# schematic.net
KiCad netlist of a schematic drawn in Altium Designer
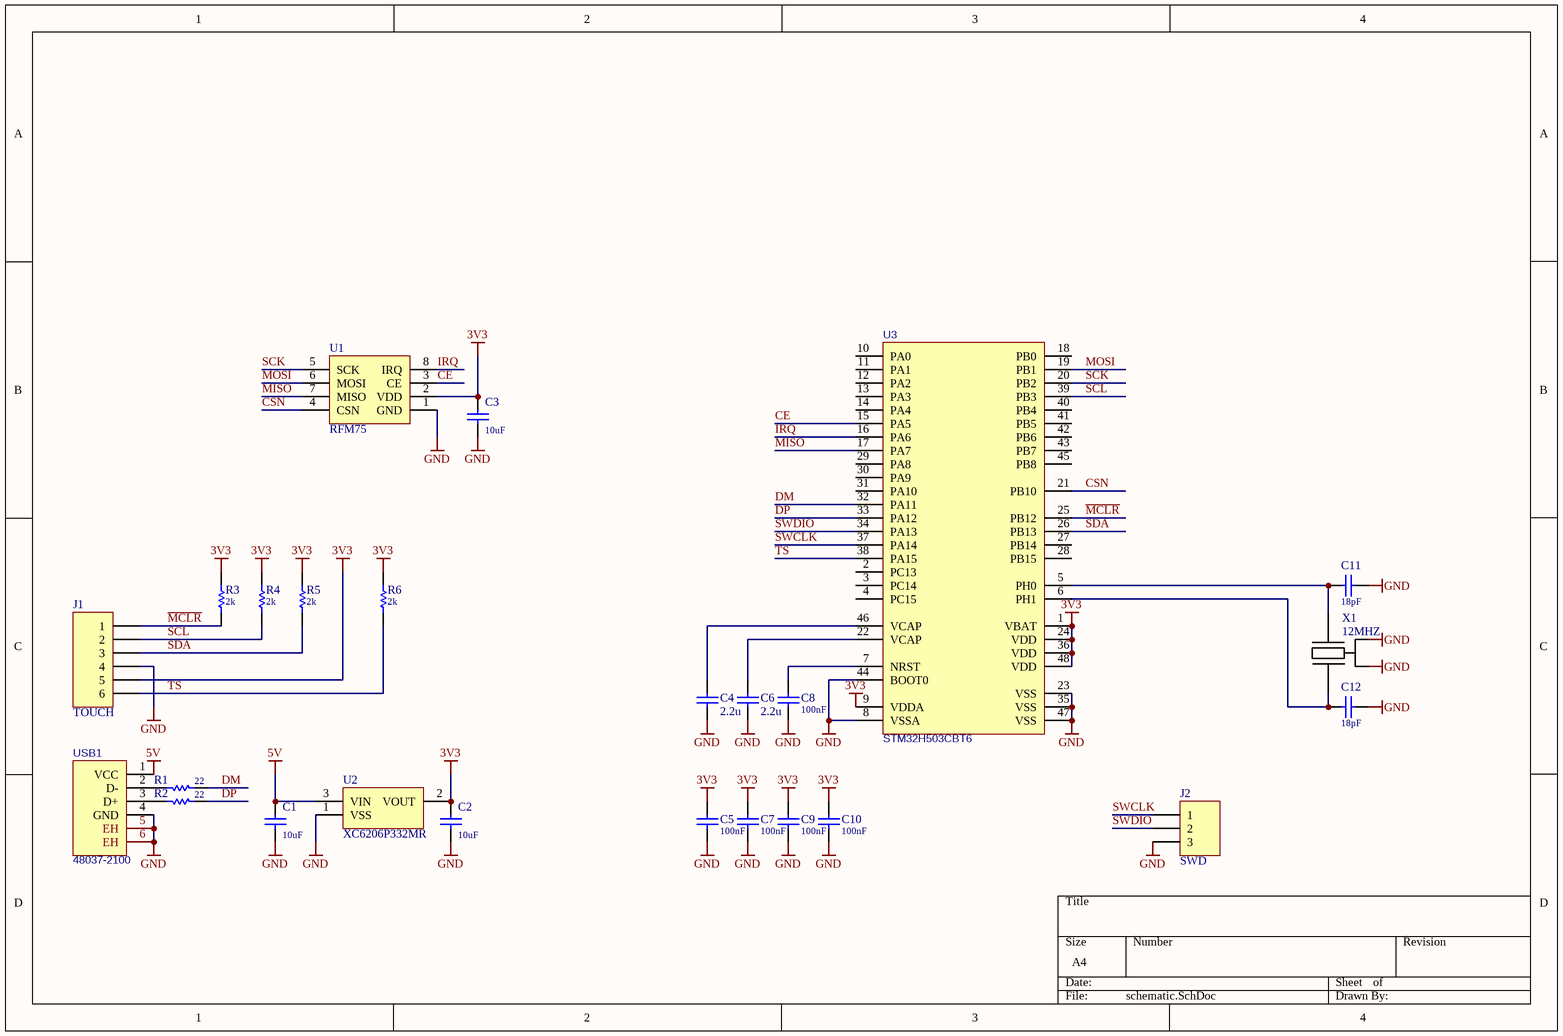
[diagram p0: schematic.SchDoc]

(export (version "E")
  (design (tool "Eeschema 10.0.6"))
  (components
    (comp (ref "C1")
      (value "10uF")
      (footprint "C0805")
      (libsource (lib "Miscellaneous Devices") (part "CAP"))
    )
    (comp (ref "C2")
      (value "10uF")
      (footprint "C0805")
      (libsource (lib "Miscellaneous Devices") (part "CAP"))
    )
    (comp (ref "C3")
      (value "10uF")
      (footprint "C0805")
      (libsource (lib "Miscellaneous Devices") (part "CAP"))
    )
    (comp (ref "C4")
      (value "2.2u")
      (footprint "C0603")
      (libsource (lib "Miscellaneous Devices") (part "Cap"))
    )
    (comp (ref "C5")
      (value "100nF")
      (footprint "C0402")
      (libsource (lib "Miscellaneous Devices") (part "CAP"))
    )
    (comp (ref "C6")
      (value "2.2u")
      (footprint "C0603")
      (libsource (lib "Miscellaneous Devices") (part "Cap"))
    )
    (comp (ref "C7")
      (value "100nF")
      (footprint "C0402")
      (libsource (lib "Miscellaneous Devices") (part "CAP"))
    )
    (comp (ref "C8")
      (value "100nF")
      (footprint "C0402")
      (libsource (lib "Miscellaneous Devices") (part "CAP"))
    )
    (comp (ref "C9")
      (value "100nF")
      (footprint "C0402")
      (libsource (lib "Miscellaneous Devices") (part "CAP"))
    )
    (comp (ref "C10")
      (value "100nF")
      (footprint "C0402")
      (libsource (lib "Miscellaneous Devices") (part "CAP"))
    )
    (comp (ref "C11")
      (value "18pF")
      (footprint "C0402")
      (description "18pF 50V 0402")
      (fields (field (name "LCSC PART NUMBER") "C33149"))
      (libsource (lib "Miscellaneous Devices") (part "CAP"))
    )
    (comp (ref "C12")
      (value "18pF")
      (footprint "C0402")
      (description "18pF 50V 0402")
      (fields (field (name "LCSC PART NUMBER") "C33149"))
      (libsource (lib "Miscellaneous Devices") (part "CAP"))
    )
    (comp (ref "J1") (value "TOUCH") (footprint "HDR-1X6_2.54") (libsource (lib "Schlib1") (part "Header 3")))
    (comp (ref "J2")
      (value "SWD")
      (footprint "HDR-1x3-P1.25")
      (libsource (lib "Miscellaneous Devices") (part "Header 3"))
    )
    (comp (ref "R1") (value "22") (footprint "R0603") (libsource (lib "Miscellaneous Devices") (part "RES")))
    (comp (ref "R2") (value "22") (footprint "R0603") (libsource (lib "Miscellaneous Devices") (part "RES")))
    (comp (ref "R3") (value "2k") (footprint "R0603") (libsource (lib "Miscellaneous Devices") (part "RES")))
    (comp (ref "R4") (value "2k") (footprint "R0603") (libsource (lib "Miscellaneous Devices") (part "RES")))
    (comp (ref "R5") (value "2k") (footprint "R0603") (libsource (lib "Miscellaneous Devices") (part "RES")))
    (comp (ref "R6") (value "2k") (footprint "R0603") (libsource (lib "Miscellaneous Devices") (part "RES")))
    (comp (ref "U1") (value "RFM75") (footprint "RFM75") (libsource (lib "Schlib1") (part "RFM75")))
    (comp (ref "U2")
      (value "XC6206P332MR")
      (footprint "SOT-23")
      (libsource (lib "Schlib1") (part "Component_4_1"))
    )
    (comp (ref "U3")
      (value "STM32H503CBT6")
      (footprint "LQFP-48")
      (libsource (lib "Schlib1") (part "STM32H503CBT6"))
    )
    (comp (ref "USB1")
      (value "48037-2100")
      (footprint "USB-A-TH_480372100")
      (fields (field (name "LCSC PART NUMBER") "C136453"))
      (libsource (lib "Schlib1") (part "48037-2100"))
    )
    (comp (ref "X1")
      (value "12MHZ")
      (footprint "CRYSTAL_2.5x2.0mm")
      (description "CRYSTAL 12MHZ 10PF SMD")
      (fields (field (name "LCSC PART NUMBER") "C284155"))
      (libsource (lib "Miscellaneous Devices") (part "CRYSTAL 12MHZ 3.20mm x 2.50mm"))
    )
  )
  (nets
    (net (code "1") (name "/CE") (class "Default")
      (node (ref "U1") (pin "3") (pinfunction "CE_3") (pintype "passive"))
      (node (ref "U3") (pin "15") (pinfunction "PA5_15") (pintype "passive"))
    )
    (net (code "2") (name "/CSN") (class "Default")
      (node (ref "U1") (pin "4") (pinfunction "CSN_4") (pintype "passive"))
      (node (ref "U3") (pin "21") (pinfunction "PB10_21") (pintype "passive"))
    )
    (net (code "3") (name "/DM") (class "Default")
      (node (ref "R1") (pin "2") (pinfunction "2_2") (pintype "passive"))
      (node (ref "U3") (pin "32") (pinfunction "PA11_32") (pintype "passive"))
    )
    (net (code "4") (name "/DP") (class "Default")
      (node (ref "R2") (pin "2") (pinfunction "2_2") (pintype "passive"))
      (node (ref "U3") (pin "33") (pinfunction "PA12_33") (pintype "passive"))
    )
    (net (code "5") (name "/IRQ") (class "Default")
      (node (ref "U1") (pin "8") (pinfunction "IRQ_8") (pintype "passive"))
      (node (ref "U3") (pin "16") (pinfunction "PA6_16") (pintype "passive"))
    )
    (net (code "6") (name "/MISO") (class "Default")
      (node (ref "U1") (pin "7") (pinfunction "MISO_7") (pintype "passive"))
      (node (ref "U3") (pin "17") (pinfunction "PA7_17") (pintype "passive"))
    )
    (net (code "7") (name "/MOSI") (class "Default")
      (node (ref "U1") (pin "6") (pinfunction "MOSI_6") (pintype "passive"))
      (node (ref "U3") (pin "19") (pinfunction "PB1_19") (pintype "passive"))
    )
    (net (code "8") (name "/SCK") (class "Default")
      (node (ref "U1") (pin "5") (pinfunction "SCK_5") (pintype "passive"))
      (node (ref "U3") (pin "20") (pinfunction "PB2_20") (pintype "passive"))
    )
    (net (code "9") (name "/SCL") (class "Default")
      (node (ref "J1") (pin "2") (pinfunction "2_2") (pintype "passive"))
      (node (ref "R4") (pin "1") (pinfunction "1_1") (pintype "passive"))
      (node (ref "U3") (pin "39") (pinfunction "PB3_39") (pintype "passive"))
    )
    (net (code "10") (name "/SDA") (class "Default")
      (node (ref "J1") (pin "3") (pinfunction "3_3") (pintype "passive"))
      (node (ref "R5") (pin "1") (pinfunction "1_1") (pintype "passive"))
      (node (ref "U3") (pin "26") (pinfunction "PB13_26") (pintype "passive"))
    )
    (net (code "11") (name "/SWCLK") (class "Default")
      (node (ref "J2") (pin "1") (pinfunction "1_1") (pintype "passive"))
      (node (ref "U3") (pin "37") (pinfunction "PA14_37") (pintype "passive"))
    )
    (net (code "12") (name "/SWDIO") (class "Default")
      (node (ref "J2") (pin "2") (pinfunction "2_2") (pintype "passive"))
      (node (ref "U3") (pin "34") (pinfunction "PA13_34") (pintype "passive"))
    )
    (net (code "13") (name "/~{MCLR}") (class "Default")
      (node (ref "J1") (pin "1") (pinfunction "1_1") (pintype "passive"))
      (node (ref "R3") (pin "1") (pinfunction "1_1") (pintype "passive"))
      (node (ref "U3") (pin "25") (pinfunction "PB12_25") (pintype "passive"))
    )
    (net (code "14") (name "/~{TS}") (class "Default")
      (node (ref "J1") (pin "6") (pinfunction "6_6") (pintype "passive"))
      (node (ref "R6") (pin "1") (pinfunction "1_1") (pintype "passive"))
      (node (ref "U3") (pin "38") (pinfunction "PA15_38") (pintype "passive"))
    )
    (net (code "15") (name "3V3") (class "Default")
      (node (ref "C10") (pin "2") (pinfunction "2_2") (pintype "passive"))
      (node (ref "C2") (pin "2") (pinfunction "2_2") (pintype "passive"))
      (node (ref "C3") (pin "2") (pinfunction "2_2") (pintype "passive"))
      (node (ref "C5") (pin "2") (pinfunction "2_2") (pintype "passive"))
      (node (ref "C7") (pin "2") (pinfunction "2_2") (pintype "passive"))
      (node (ref "C9") (pin "2") (pinfunction "2_2") (pintype "passive"))
      (node (ref "J1") (pin "5") (pinfunction "5_5") (pintype "passive"))
      (node (ref "R3") (pin "2") (pinfunction "2_2") (pintype "passive"))
      (node (ref "R4") (pin "2") (pinfunction "2_2") (pintype "passive"))
      (node (ref "R5") (pin "2") (pinfunction "2_2") (pintype "passive"))
      (node (ref "R6") (pin "2") (pinfunction "2_2") (pintype "passive"))
      (node (ref "U1") (pin "2") (pinfunction "VDD_2") (pintype "passive"))
      (node (ref "U2") (pin "2") (pinfunction "VOUT_2") (pintype "passive"))
      (node (ref "U3") (pin "1") (pinfunction "VBAT_1") (pintype "passive"))
      (node (ref "U3") (pin "24") (pinfunction "VDD_24") (pintype "passive"))
      (node (ref "U3") (pin "36") (pinfunction "VDD_36") (pintype "passive"))
      (node (ref "U3") (pin "48") (pinfunction "VDD_48") (pintype "passive"))
      (node (ref "U3") (pin "9") (pinfunction "VDDA_9") (pintype "passive"))
    )
    (net (code "16") (name "5V") (class "Default")
      (node (ref "C1") (pin "2") (pinfunction "2_2") (pintype "passive"))
      (node (ref "U2") (pin "3") (pinfunction "VIN_3") (pintype "passive"))
      (node (ref "USB1") (pin "1") (pinfunction "VCC_1") (pintype "passive"))
    )
    (net (code "17") (name "GND") (class "Default")
      (node (ref "C1") (pin "1") (pinfunction "1_1") (pintype "passive"))
      (node (ref "C10") (pin "1") (pinfunction "1_1") (pintype "passive"))
      (node (ref "C11") (pin "1") (pinfunction "1_1") (pintype "passive"))
      (node (ref "C12") (pin "1") (pinfunction "1_1") (pintype "passive"))
      (node (ref "C2") (pin "1") (pinfunction "1_1") (pintype "passive"))
      (node (ref "C3") (pin "1") (pinfunction "1_1") (pintype "passive"))
      (node (ref "C4") (pin "1") (pinfunction "1_1") (pintype "passive"))
      (node (ref "C5") (pin "1") (pinfunction "1_1") (pintype "passive"))
      (node (ref "C6") (pin "1") (pinfunction "1_1") (pintype "passive"))
      (node (ref "C7") (pin "1") (pinfunction "1_1") (pintype "passive"))
      (node (ref "C8") (pin "1") (pinfunction "1_1") (pintype "passive"))
      (node (ref "C9") (pin "1") (pinfunction "1_1") (pintype "passive"))
      (node (ref "J1") (pin "4") (pinfunction "4_4") (pintype "passive"))
      (node (ref "J2") (pin "3") (pinfunction "3_3") (pintype "passive"))
      (node (ref "U1") (pin "1") (pinfunction "GND_1") (pintype "passive"))
      (node (ref "U2") (pin "1") (pinfunction "VSS_1") (pintype "passive"))
      (node (ref "U3") (pin "23") (pinfunction "VSS_23") (pintype "passive"))
      (node (ref "U3") (pin "35") (pinfunction "VSS_35") (pintype "passive"))
      (node (ref "U3") (pin "44") (pinfunction "BOOT0_44") (pintype "passive"))
      (node (ref "U3") (pin "47") (pinfunction "VSS_47") (pintype "passive"))
      (node (ref "U3") (pin "8") (pinfunction "VSSA_8") (pintype "passive"))
      (node (ref "USB1") (pin "4") (pinfunction "GND_4") (pintype "passive"))
      (node (ref "USB1") (pin "5") (pinfunction "EH_5") (pintype "passive"))
      (node (ref "USB1") (pin "6") (pinfunction "EH_6") (pintype "passive"))
      (node (ref "X1") (pin "2") (pinfunction "GND_2") (pintype "passive"))
      (node (ref "X1") (pin "4") (pinfunction "GND_4") (pintype "passive"))
    )
    (net (code "18") (name "Net-(C4-Pad2)") (class "Default")
      (node (ref "C4") (pin "2") (pinfunction "2_2") (pintype "passive"))
      (node (ref "U3") (pin "46") (pinfunction "VCAP_46") (pintype "passive"))
    )
    (net (code "19") (name "Net-(C6-Pad2)") (class "Default")
      (node (ref "C6") (pin "2") (pinfunction "2_2") (pintype "passive"))
      (node (ref "U3") (pin "22") (pinfunction "VCAP_22") (pintype "passive"))
    )
    (net (code "20") (name "Net-(U3-NRST)") (class "Default")
      (node (ref "C8") (pin "2") (pinfunction "2_2") (pintype "passive"))
      (node (ref "U3") (pin "7") (pinfunction "NRST_7") (pintype "passive"))
    )
    (net (code "21") (name "Net-(U3-PH0)") (class "Default")
      (node (ref "C11") (pin "2") (pinfunction "2_2") (pintype "passive"))
      (node (ref "U3") (pin "5") (pinfunction "PH0_5") (pintype "passive"))
      (node (ref "X1") (pin "3") (pinfunction "X2_3") (pintype "passive"))
    )
    (net (code "22") (name "Net-(U3-PH1)") (class "Default")
      (node (ref "C12") (pin "2") (pinfunction "2_2") (pintype "passive"))
      (node (ref "U3") (pin "6") (pinfunction "PH1_6") (pintype "passive"))
      (node (ref "X1") (pin "1") (pinfunction "X1_1") (pintype "passive"))
    )
    (net (code "23") (name "Net-(USB1-D+)") (class "Default")
      (node (ref "R2") (pin "1") (pinfunction "1_1") (pintype "passive"))
      (node (ref "USB1") (pin "3") (pinfunction "D+_3") (pintype "passive"))
    )
    (net (code "24") (name "Net-(USB1-D-)") (class "Default")
      (node (ref "R1") (pin "1") (pinfunction "1_1") (pintype "passive"))
      (node (ref "USB1") (pin "2") (pinfunction "D-_2") (pintype "passive"))
    )
    (net (code "25") (name "unconnected-(U3-PA0-Pad10)") (class "Default")
      (node (ref "U3") (pin "10") (pinfunction "PA0_10") (pintype "passive"))
    )
    (net (code "26") (name "unconnected-(U3-PA1-Pad11)") (class "Default")
      (node (ref "U3") (pin "11") (pinfunction "PA1_11") (pintype "passive"))
    )
    (net (code "27") (name "unconnected-(U3-PA2-Pad12)") (class "Default")
      (node (ref "U3") (pin "12") (pinfunction "PA2_12") (pintype "passive"))
    )
    (net (code "28") (name "unconnected-(U3-PA3-Pad13)") (class "Default")
      (node (ref "U3") (pin "13") (pinfunction "PA3_13") (pintype "passive"))
    )
    (net (code "29") (name "unconnected-(U3-PA4-Pad14)") (class "Default")
      (node (ref "U3") (pin "14") (pinfunction "PA4_14") (pintype "passive"))
    )
    (net (code "30") (name "unconnected-(U3-PA8-Pad29)") (class "Default")
      (node (ref "U3") (pin "29") (pinfunction "PA8_29") (pintype "passive"))
    )
    (net (code "31") (name "unconnected-(U3-PA9-Pad30)") (class "Default")
      (node (ref "U3") (pin "30") (pinfunction "PA9_30") (pintype "passive"))
    )
    (net (code "32") (name "unconnected-(U3-PA10-Pad31)") (class "Default")
      (node (ref "U3") (pin "31") (pinfunction "PA10_31") (pintype "passive"))
    )
    (net (code "33") (name "unconnected-(U3-PB0-Pad18)") (class "Default")
      (node (ref "U3") (pin "18") (pinfunction "PB0_18") (pintype "passive"))
    )
    (net (code "34") (name "unconnected-(U3-PB4-Pad40)") (class "Default")
      (node (ref "U3") (pin "40") (pinfunction "PB4_40") (pintype "passive"))
    )
    (net (code "35") (name "unconnected-(U3-PB5-Pad41)") (class "Default")
      (node (ref "U3") (pin "41") (pinfunction "PB5_41") (pintype "passive"))
    )
    (net (code "36") (name "unconnected-(U3-PB6-Pad42)") (class "Default")
      (node (ref "U3") (pin "42") (pinfunction "PB6_42") (pintype "passive"))
    )
    (net (code "37") (name "unconnected-(U3-PB7-Pad43)") (class "Default")
      (node (ref "U3") (pin "43") (pinfunction "PB7_43") (pintype "passive"))
    )
    (net (code "38") (name "unconnected-(U3-PB8-Pad45)") (class "Default")
      (node (ref "U3") (pin "45") (pinfunction "PB8_45") (pintype "passive"))
    )
    (net (code "39") (name "unconnected-(U3-PB14-Pad27)") (class "Default")
      (node (ref "U3") (pin "27") (pinfunction "PB14_27") (pintype "passive"))
    )
    (net (code "40") (name "unconnected-(U3-PB15-Pad28)") (class "Default")
      (node (ref "U3") (pin "28") (pinfunction "PB15_28") (pintype "passive"))
    )
    (net (code "41") (name "unconnected-(U3-PC13-Pad2)") (class "Default")
      (node (ref "U3") (pin "2") (pinfunction "PC13_2") (pintype "passive"))
    )
    (net (code "42") (name "unconnected-(U3-PC14-Pad3)") (class "Default")
      (node (ref "U3") (pin "3") (pinfunction "PC14_3") (pintype "passive"))
    )
    (net (code "43") (name "unconnected-(U3-PC15-Pad4)") (class "Default")
      (node (ref "U3") (pin "4") (pinfunction "PC15_4") (pintype "passive"))
    )
  )
)
